# Top_Level.net
KiCad netlist of a schematic drawn in Altium Designer
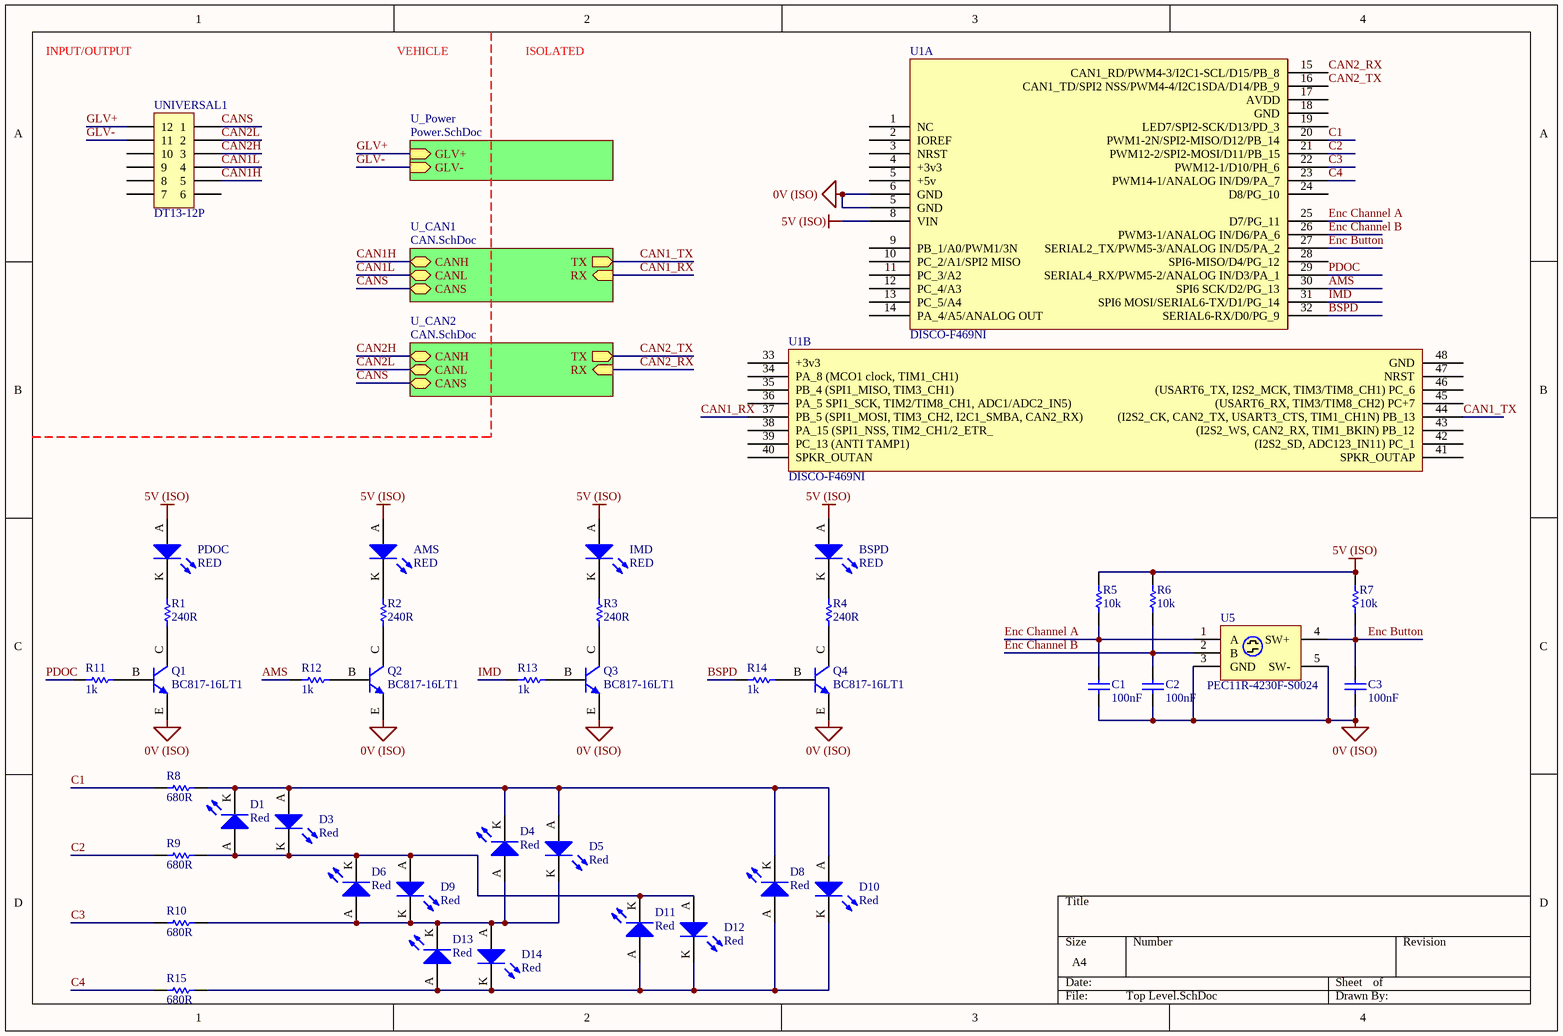
[diagram p0: Top Level.SchDoc]

(export (version "E")
  (design (tool "Eeschema 10.0.6"))
  (components
    (comp (ref "AMS")
      (value "RED")
      (footprint "5MM LED")
      (description "LED RED CLEAR 5MM ROUND T/H")
      (fields (field (name "PART NUMBER") "C503B-GAN-CB0F0791") (field (name "MANUFACTURER") "Cree Inc."))
      (libsource (lib "ts_19-standard-library") (part "LED"))
    )
    (comp (ref "BSPD")
      (value "RED")
      (footprint "5MM LED")
      (description "LED RED CLEAR 5MM ROUND T/H")
      (fields (field (name "PART NUMBER") "C503B-GAN-CB0F0791") (field (name "MANUFACTURER") "Cree Inc."))
      (libsource (lib "ts_19-standard-library") (part "LED"))
    )
    (comp (ref "C1")
      (value "100nF")
      (footprint "0805")
      (fields
        (field (name "PART NUMBER") "GCM21BR71E104KA37L")
        (field (name "TOLERANCE") "10%")
        (field (name "MANUFACTURER") "muRata")
      )
      (libsource (lib "ts_19-standard-library") (part "Capacitor"))
    )
    (comp (ref "C2")
      (value "100nF")
      (footprint "0805")
      (fields
        (field (name "PART NUMBER") "GCM21BR71E104KA37L")
        (field (name "TOLERANCE") "10%")
        (field (name "MANUFACTURER") "muRata")
      )
      (libsource (lib "ts_19-standard-library") (part "Capacitor"))
    )
    (comp (ref "C3")
      (value "100nF")
      (footprint "0805")
      (fields
        (field (name "PART NUMBER") "GCM21BR71E104KA37L")
        (field (name "TOLERANCE") "10%")
        (field (name "MANUFACTURER") "muRata")
      )
      (libsource (lib "ts_19-standard-library") (part "Capacitor"))
    )
    (comp (ref "D1")
      (value "Red")
      (footprint "0805 LED")
      (description "Red LED Indication - Discrete 1.75V 0805 (2012 Metric)")
      (fields (field (name "MANUFACTURER") "ROHM Semiconductor") (field (name "PART NUMBER") "SML-210LTT86"))
      (libsource (lib "ts_19-standard-library") (part "LED"))
    )
    (comp (ref "D3")
      (value "Red")
      (footprint "0805 LED")
      (description "Red LED Indication - Discrete 1.75V 0805 (2012 Metric)")
      (fields (field (name "MANUFACTURER") "ROHM Semiconductor") (field (name "PART NUMBER") "SML-210LTT86"))
      (libsource (lib "ts_19-standard-library") (part "LED"))
    )
    (comp (ref "D4")
      (value "Red")
      (footprint "0805 LED")
      (description "Red LED Indication - Discrete 1.75V 0805 (2012 Metric)")
      (fields (field (name "MANUFACTURER") "ROHM Semiconductor") (field (name "PART NUMBER") "SML-210LTT86"))
      (libsource (lib "ts_19-standard-library") (part "LED"))
    )
    (comp (ref "D5")
      (value "Red")
      (footprint "0805 LED")
      (description "Red LED Indication - Discrete 1.75V 0805 (2012 Metric)")
      (fields (field (name "MANUFACTURER") "ROHM Semiconductor") (field (name "PART NUMBER") "SML-210LTT86"))
      (libsource (lib "ts_19-standard-library") (part "LED"))
    )
    (comp (ref "D6")
      (value "Red")
      (footprint "0805 LED")
      (description "Red LED Indication - Discrete 1.75V 0805 (2012 Metric)")
      (fields (field (name "MANUFACTURER") "ROHM Semiconductor") (field (name "PART NUMBER") "SML-210LTT86"))
      (libsource (lib "ts_19-standard-library") (part "LED"))
    )
    (comp (ref "D8")
      (value "Red")
      (footprint "0805 LED")
      (description "Red LED Indication - Discrete 1.75V 0805 (2012 Metric)")
      (fields (field (name "MANUFACTURER") "ROHM Semiconductor") (field (name "PART NUMBER") "SML-210LTT86"))
      (libsource (lib "ts_19-standard-library") (part "LED"))
    )
    (comp (ref "D9")
      (value "Red")
      (footprint "0805 LED")
      (description "Red LED Indication - Discrete 1.75V 0805 (2012 Metric)")
      (fields (field (name "MANUFACTURER") "ROHM Semiconductor") (field (name "PART NUMBER") "SML-210LTT86"))
      (libsource (lib "ts_19-standard-library") (part "LED"))
    )
    (comp (ref "D10")
      (value "Red")
      (footprint "0805 LED")
      (description "Red LED Indication - Discrete 1.75V 0805 (2012 Metric)")
      (fields (field (name "MANUFACTURER") "ROHM Semiconductor") (field (name "PART NUMBER") "SML-210LTT86"))
      (libsource (lib "ts_19-standard-library") (part "LED"))
    )
    (comp (ref "D11")
      (value "Red")
      (footprint "0805 LED")
      (description "Red LED Indication - Discrete 1.75V 0805 (2012 Metric)")
      (fields (field (name "MANUFACTURER") "ROHM Semiconductor") (field (name "PART NUMBER") "SML-210LTT86"))
      (libsource (lib "ts_19-standard-library") (part "LED"))
    )
    (comp (ref "D12")
      (value "Red")
      (footprint "0805 LED")
      (description "Red LED Indication - Discrete 1.75V 0805 (2012 Metric)")
      (fields (field (name "MANUFACTURER") "ROHM Semiconductor") (field (name "PART NUMBER") "SML-210LTT86"))
      (libsource (lib "ts_19-standard-library") (part "LED"))
    )
    (comp (ref "D13")
      (value "Red")
      (footprint "0805 LED")
      (description "Red LED Indication - Discrete 1.75V 0805 (2012 Metric)")
      (fields (field (name "MANUFACTURER") "ROHM Semiconductor") (field (name "PART NUMBER") "SML-210LTT86"))
      (libsource (lib "ts_19-standard-library") (part "LED"))
    )
    (comp (ref "D14")
      (value "Red")
      (footprint "0805 LED")
      (description "Red LED Indication - Discrete 1.75V 0805 (2012 Metric)")
      (fields (field (name "MANUFACTURER") "ROHM Semiconductor") (field (name "PART NUMBER") "SML-210LTT86"))
      (libsource (lib "ts_19-standard-library") (part "LED"))
    )
    (comp (ref "IMD")
      (value "RED")
      (footprint "5MM LED")
      (description "LED RED CLEAR 5MM ROUND T/H")
      (fields (field (name "PART NUMBER") "C503B-GAN-CB0F0791") (field (name "MANUFACTURER") "Cree Inc."))
      (libsource (lib "ts_19-standard-library") (part "LED"))
    )
    (comp (ref "PDOC")
      (value "RED")
      (footprint "5MM LED")
      (description "LED RED CLEAR 5MM ROUND T/H")
      (fields (field (name "PART NUMBER") "C503B-GAN-CB0F0791") (field (name "MANUFACTURER") "Cree Inc."))
      (libsource (lib "ts_19-standard-library") (part "LED"))
    )
    (comp (ref "Q1")
      (value "BC817-16LT1")
      (footprint "ON SOT-23 BJT")
      (description "300mW  BJT NPN Transistor")
      (fields
        (field (name "MANUFACTURER") "ON Semiconductor")
        (field (name "DIGIKEY PART NUMBER") "BC817-16LT1OSTR-ND")
      )
      (libsource (lib "ts_19-standard-library") (part "NPN"))
    )
    (comp (ref "Q2")
      (value "BC817-16LT1")
      (footprint "ON SOT-23 BJT")
      (description "300mW  BJT NPN Transistor")
      (fields
        (field (name "MANUFACTURER") "ON Semiconductor")
        (field (name "DIGIKEY PART NUMBER") "BC817-16LT1OSTR-ND")
      )
      (libsource (lib "ts_19-standard-library") (part "NPN"))
    )
    (comp (ref "Q3")
      (value "BC817-16LT1")
      (footprint "ON SOT-23 BJT")
      (description "300mW  BJT NPN Transistor")
      (fields
        (field (name "MANUFACTURER") "ON Semiconductor")
        (field (name "DIGIKEY PART NUMBER") "BC817-16LT1OSTR-ND")
      )
      (libsource (lib "ts_19-standard-library") (part "NPN"))
    )
    (comp (ref "Q4")
      (value "BC817-16LT1")
      (footprint "ON SOT-23 BJT")
      (description "300mW  BJT NPN Transistor")
      (fields
        (field (name "MANUFACTURER") "ON Semiconductor")
        (field (name "DIGIKEY PART NUMBER") "BC817-16LT1OSTR-ND")
      )
      (libsource (lib "ts_19-standard-library") (part "NPN"))
    )
    (comp (ref "R1")
      (value "240R")
      (footprint "0805")
      (fields
        (field (name "PART NUMBER") "RC0805FR07240RL")
        (field (name "MANUFACTURER") "YAGEO")
        (field (name "TOLERANCE") "0.01")
      )
      (libsource (lib "ts_19-standard-library") (part "Resistor"))
    )
    (comp (ref "R2")
      (value "240R")
      (footprint "0805")
      (fields
        (field (name "PART NUMBER") "RC0805FR07240RL")
        (field (name "MANUFACTURER") "YAGEO")
        (field (name "TOLERANCE") "0.01")
      )
      (libsource (lib "ts_19-standard-library") (part "Resistor"))
    )
    (comp (ref "R3")
      (value "240R")
      (footprint "0805")
      (fields
        (field (name "PART NUMBER") "RC0805FR07240RL")
        (field (name "MANUFACTURER") "YAGEO")
        (field (name "TOLERANCE") "0.01")
      )
      (libsource (lib "ts_19-standard-library") (part "Resistor"))
    )
    (comp (ref "R4")
      (value "240R")
      (footprint "0805")
      (fields
        (field (name "PART NUMBER") "RC0805FR07240RL")
        (field (name "MANUFACTURER") "YAGEO")
        (field (name "TOLERANCE") "0.01")
      )
      (libsource (lib "ts_19-standard-library") (part "Resistor"))
    )
    (comp (ref "R5")
      (value "10k")
      (footprint "0805")
      (fields
        (field (name "PART NUMBER") "RC0805FR0710KL")
        (field (name "MANUFACTURER") "YAGEO")
        (field (name "TOLERANCE") "0.01")
      )
      (libsource (lib "ts_19-standard-library") (part "Resistor"))
    )
    (comp (ref "R6")
      (value "10k")
      (footprint "0805")
      (fields
        (field (name "PART NUMBER") "RC0805FR0710KL")
        (field (name "MANUFACTURER") "YAGEO")
        (field (name "TOLERANCE") "0.01")
      )
      (libsource (lib "ts_19-standard-library") (part "Resistor"))
    )
    (comp (ref "R7")
      (value "10k")
      (footprint "0805")
      (fields
        (field (name "PART NUMBER") "RC0805FR0710KL")
        (field (name "MANUFACTURER") "YAGEO")
        (field (name "TOLERANCE") "0.01")
      )
      (libsource (lib "ts_19-standard-library") (part "Resistor"))
    )
    (comp (ref "R8")
      (value "680R")
      (footprint "0805")
      (fields
        (field (name "MANUFACTURER") "YAGEO")
        (field (name "PART NUMBER") "RC0805FR07680RL")
        (field (name "TOLERANCE") "0.01")
      )
      (libsource (lib "ts_19-standard-library") (part "Resistor"))
    )
    (comp (ref "R9")
      (value "680R")
      (footprint "0805")
      (fields
        (field (name "MANUFACTURER") "YAGEO")
        (field (name "PART NUMBER") "RC0805FR07680RL")
        (field (name "TOLERANCE") "0.01")
      )
      (libsource (lib "ts_19-standard-library") (part "Resistor"))
    )
    (comp (ref "R10")
      (value "680R")
      (footprint "0805")
      (fields
        (field (name "MANUFACTURER") "YAGEO")
        (field (name "PART NUMBER") "RC0805FR07680RL")
        (field (name "TOLERANCE") "0.01")
      )
      (libsource (lib "ts_19-standard-library") (part "Resistor"))
    )
    (comp (ref "R11")
      (value "1k")
      (footprint "0805")
      (fields
        (field (name "PART NUMBER") "RC0805FR071KL")
        (field (name "MANUFACTURER") "YAGEO")
        (field (name "TOLERANCE") "0.01")
      )
      (libsource (lib "ts_19-standard-library") (part "Resistor"))
    )
    (comp (ref "R12")
      (value "1k")
      (footprint "0805")
      (fields
        (field (name "PART NUMBER") "RC0805FR071KL")
        (field (name "MANUFACTURER") "YAGEO")
        (field (name "TOLERANCE") "0.01")
      )
      (libsource (lib "ts_19-standard-library") (part "Resistor"))
    )
    (comp (ref "R13")
      (value "1k")
      (footprint "0805")
      (fields
        (field (name "PART NUMBER") "RC0805FR071KL")
        (field (name "MANUFACTURER") "YAGEO")
        (field (name "TOLERANCE") "0.01")
      )
      (libsource (lib "ts_19-standard-library") (part "Resistor"))
    )
    (comp (ref "R14")
      (value "1k")
      (footprint "0805")
      (fields
        (field (name "PART NUMBER") "RC0805FR071KL")
        (field (name "MANUFACTURER") "YAGEO")
        (field (name "TOLERANCE") "0.01")
      )
      (libsource (lib "ts_19-standard-library") (part "Resistor"))
    )
    (comp (ref "R15")
      (value "680R")
      (footprint "0805")
      (fields
        (field (name "MANUFACTURER") "YAGEO")
        (field (name "PART NUMBER") "RC0805FR07680RL")
        (field (name "TOLERANCE") "0.01")
      )
      (libsource (lib "ts_19-standard-library") (part "Resistor"))
    )
    (comp (ref "U1")
      (value "DISCO-F469NI")
      (footprint "DISCO-F469NI")
      (fields
        (field (name "MANUFACTURER") "STMicroelectronics")
        (field (name "DIGIKEY PART NUMBER") "497-15990-ND")
      )
      (libsource (lib "ts_19-standard-library") (part "DISCO-F469NI"))
    )
    (comp (ref "U5")
      (value "PEC11R-4230F-S0024")
      (footprint "PEC11R-4230F-S0024-ND")
      (description "Quadrature Rotary encoder w/ pushbutton")
      (fields
        (field (name "MANUFACTURER") "Bourns Inc.")
        (field (name "DIGIKEY PART NUMBER") "PEC11R-4230F-S0024-ND")
      )
      (libsource (lib "ts_19-standard-library") (part "PEC11R-4230F-S0024-ND"))
    )
    (comp (ref "UNIVERSAL1")
      (value "DT13-12P")
      (footprint "DT13-12P")
      (fields (field (name "DIGIKEY PART NUMBER") "1734-1451-ND") (field (name "CONTACT") "Nickel"))
      (libsource (lib "ts_19-standard-connectors") (part "DT13-12P"))
    )
  )
  (nets
    (net (code "1") (name "/AMS") (class "Default")
      (node (ref "R12") (pin "1") (pinfunction "1_1") (pintype "passive"))
      (node (ref "U1") (pin "30") (pinfunction "SPI6_SCK/D2/PG_13_30") (pintype "passive"))
    )
    (net (code "2") (name "/BSPD") (class "Default")
      (node (ref "R14") (pin "1") (pinfunction "1_1") (pintype "passive"))
      (node (ref "U1") (pin "32") (pinfunction "SERIAL6-RX/D0/PG_9_32") (pintype "passive"))
    )
    (net (code "3") (name "/C1") (class "Default")
      (node (ref "R8") (pin "2") (pinfunction "2_2") (pintype "passive"))
      (node (ref "U1") (pin "20") (pinfunction "PWM1-2N/SPI2-MISO/D12/PB_14_20") (pintype "passive"))
    )
    (net (code "4") (name "/C2") (class "Default")
      (node (ref "R9") (pin "2") (pinfunction "2_2") (pintype "passive"))
      (node (ref "U1") (pin "21") (pinfunction "PWM12-2/SPI2-MOSI/D11/PB_15_21") (pintype "passive"))
    )
    (net (code "5") (name "/C3") (class "Default")
      (node (ref "R10") (pin "2") (pinfunction "2_2") (pintype "passive"))
      (node (ref "U1") (pin "22") (pinfunction "PWM12-1/D10/PH_6_22") (pintype "passive"))
    )
    (net (code "6") (name "/C4") (class "Default")
      (node (ref "R15") (pin "2") (pinfunction "2_2") (pintype "passive"))
      (node (ref "U1") (pin "23") (pinfunction "PWM14-1/ANALOG_IN/D9/PA_7_23") (pintype "passive"))
    )
    (net (code "7") (name "/CAN1H") (class "Default")
      (node (ref "UNIVERSAL1") (pin "5") (pinfunction "5_5") (pintype "power_in"))
    )
    (net (code "8") (name "/CAN1L") (class "Default")
      (node (ref "UNIVERSAL1") (pin "4") (pinfunction "4_4") (pintype "power_in"))
    )
    (net (code "9") (name "/CAN1_RX") (class "Default")
      (node (ref "U1") (pin "37") (pinfunction "PB_5_(SPI1_MOSI,_TIM3_CH2,_I2C1_SMBA,_CAN2_RX)_37") (pintype "passive"))
    )
    (net (code "10") (name "/CAN1_TX") (class "Default")
      (node (ref "U1") (pin "44") (pinfunction "(I2S2_CK,_CAN2_TX,_USART3_CTS,_TIM1_CH1N)_PB_13_44") (pintype "passive"))
    )
    (net (code "11") (name "/CAN2H") (class "Default")
      (node (ref "UNIVERSAL1") (pin "3") (pinfunction "3_3") (pintype "power_in"))
    )
    (net (code "12") (name "/CAN2L") (class "Default")
      (node (ref "UNIVERSAL1") (pin "2") (pinfunction "2_2") (pintype "power_in"))
    )
    (net (code "13") (name "/CAN2_RX") (class "Default")
      (node (ref "U1") (pin "15") (pinfunction "CAN1_RD/PWM4-3/I2C1-SCL/D15/PB_8_15") (pintype "passive"))
    )
    (net (code "14") (name "/CAN2_TX") (class "Default")
      (node (ref "U1") (pin "16") (pinfunction "CAN1_TD/SPI2_NSS/PWM4-4/I2C1SDA/D14/PB_9_16") (pintype "passive"))
    )
    (net (code "15") (name "/CANS") (class "Default")
      (node (ref "UNIVERSAL1") (pin "1") (pinfunction "1_1") (pintype "power_in"))
    )
    (net (code "16") (name "/Enc Button") (class "Default")
      (node (ref "C3") (pin "2") (pinfunction "2_2") (pintype "passive"))
      (node (ref "R7") (pin "1") (pinfunction "1_1") (pintype "passive"))
      (node (ref "U1") (pin "27") (pinfunction "SERIAL2_TX/PWM5-3/ANALOG_IN/D5/PA_2_27") (pintype "passive"))
      (node (ref "U5") (pin "4") (pinfunction "SW+_4") (pintype "passive"))
    )
    (net (code "17") (name "/Enc Channel A") (class "Default")
      (node (ref "C1") (pin "2") (pinfunction "2_2") (pintype "passive"))
      (node (ref "R5") (pin "1") (pinfunction "1_1") (pintype "passive"))
      (node (ref "U1") (pin "25") (pinfunction "D7/PG_11_25") (pintype "passive"))
      (node (ref "U5") (pin "1") (pinfunction "A_1") (pintype "passive"))
    )
    (net (code "18") (name "/Enc Channel B") (class "Default")
      (node (ref "C2") (pin "2") (pinfunction "2_2") (pintype "passive"))
      (node (ref "R6") (pin "1") (pinfunction "1_1") (pintype "passive"))
      (node (ref "U1") (pin "26") (pinfunction "PWM3-1/ANALOG_IN/D6/PA_6_26") (pintype "passive"))
      (node (ref "U5") (pin "2") (pinfunction "B_2") (pintype "passive"))
    )
    (net (code "19") (name "/GLV+") (class "Default")
      (node (ref "UNIVERSAL1") (pin "12") (pinfunction "12_12") (pintype "passive"))
    )
    (net (code "20") (name "/GLV-") (class "Default")
      (node (ref "UNIVERSAL1") (pin "11") (pinfunction "11_11") (pintype "passive"))
    )
    (net (code "21") (name "/IMD") (class "Default")
      (node (ref "R13") (pin "1") (pinfunction "1_1") (pintype "passive"))
      (node (ref "U1") (pin "31") (pinfunction "SPI6_MOSI/SERIAL6-TX/D1/PG_14_31") (pintype "passive"))
    )
    (net (code "22") (name "/PDOC") (class "Default")
      (node (ref "R11") (pin "1") (pinfunction "1_1") (pintype "passive"))
      (node (ref "U1") (pin "29") (pinfunction "SERIAL4_RX/PWM5-2/ANALOG_IN/D3/PA_1_29") (pintype "passive"))
    )
    (net (code "23") (name "0V (ISO)") (class "Default")
      (node (ref "C1") (pin "1") (pinfunction "1_1") (pintype "passive"))
      (node (ref "C2") (pin "1") (pinfunction "1_1") (pintype "passive"))
      (node (ref "C3") (pin "1") (pinfunction "1_1") (pintype "passive"))
      (node (ref "Q1") (pin "E") (pinfunction "E_E") (pintype "passive"))
      (node (ref "Q2") (pin "E") (pinfunction "E_E") (pintype "passive"))
      (node (ref "Q3") (pin "E") (pinfunction "E_E") (pintype "passive"))
      (node (ref "Q4") (pin "E") (pinfunction "E_E") (pintype "passive"))
      (node (ref "U1") (pin "5") (pinfunction "GND_5") (pintype "passive"))
      (node (ref "U1") (pin "6") (pinfunction "GND_6") (pintype "passive"))
      (node (ref "U5") (pin "3") (pinfunction "GND_3") (pintype "passive"))
      (node (ref "U5") (pin "5") (pinfunction "SW-_5") (pintype "passive"))
    )
    (net (code "24") (name "5V (ISO)") (class "Default")
      (node (ref "AMS") (pin "A") (pinfunction "A_A") (pintype "passive"))
      (node (ref "BSPD") (pin "A") (pinfunction "A_A") (pintype "passive"))
      (node (ref "IMD") (pin "A") (pinfunction "A_A") (pintype "passive"))
      (node (ref "PDOC") (pin "A") (pinfunction "A_A") (pintype "passive"))
      (node (ref "R5") (pin "2") (pinfunction "2_2") (pintype "passive"))
      (node (ref "R6") (pin "2") (pinfunction "2_2") (pintype "passive"))
      (node (ref "R7") (pin "2") (pinfunction "2_2") (pintype "passive"))
      (node (ref "U1") (pin "8") (pinfunction "VIN_8") (pintype "passive"))
    )
    (net (code "25") (name "Net-(AMS-PadK)") (class "Default")
      (node (ref "AMS") (pin "K") (pinfunction "K_K") (pintype "passive"))
      (node (ref "R2") (pin "2") (pinfunction "2_2") (pintype "passive"))
    )
    (net (code "26") (name "Net-(BSPD-PadK)") (class "Default")
      (node (ref "BSPD") (pin "K") (pinfunction "K_K") (pintype "passive"))
      (node (ref "R4") (pin "2") (pinfunction "2_2") (pintype "passive"))
    )
    (net (code "27") (name "Net-(D1-PadA)") (class "Default")
      (node (ref "D1") (pin "A") (pinfunction "A_A") (pintype "passive"))
      (node (ref "D11") (pin "K") (pinfunction "K_K") (pintype "passive"))
      (node (ref "D12") (pin "A") (pinfunction "A_A") (pintype "passive"))
      (node (ref "D3") (pin "K") (pinfunction "K_K") (pintype "passive"))
      (node (ref "D6") (pin "K") (pinfunction "K_K") (pintype "passive"))
      (node (ref "D9") (pin "A") (pinfunction "A_A") (pintype "passive"))
      (node (ref "R9") (pin "1") (pinfunction "1_1") (pintype "passive"))
    )
    (net (code "28") (name "Net-(D1-PadK)") (class "Default")
      (node (ref "D1") (pin "K") (pinfunction "K_K") (pintype "passive"))
      (node (ref "D10") (pin "A") (pinfunction "A_A") (pintype "passive"))
      (node (ref "D3") (pin "A") (pinfunction "A_A") (pintype "passive"))
      (node (ref "D4") (pin "K") (pinfunction "K_K") (pintype "passive"))
      (node (ref "D5") (pin "A") (pinfunction "A_A") (pintype "passive"))
      (node (ref "D8") (pin "K") (pinfunction "K_K") (pintype "passive"))
      (node (ref "R8") (pin "1") (pinfunction "1_1") (pintype "passive"))
    )
    (net (code "29") (name "Net-(D10-PadK)") (class "Default")
      (node (ref "D10") (pin "K") (pinfunction "K_K") (pintype "passive"))
      (node (ref "D11") (pin "A") (pinfunction "A_A") (pintype "passive"))
      (node (ref "D12") (pin "K") (pinfunction "K_K") (pintype "passive"))
      (node (ref "D13") (pin "A") (pinfunction "A_A") (pintype "passive"))
      (node (ref "D14") (pin "K") (pinfunction "K_K") (pintype "passive"))
      (node (ref "D8") (pin "A") (pinfunction "A_A") (pintype "passive"))
      (node (ref "R15") (pin "1") (pinfunction "1_1") (pintype "passive"))
    )
    (net (code "30") (name "Net-(D13-PadK)") (class "Default")
      (node (ref "D13") (pin "K") (pinfunction "K_K") (pintype "passive"))
      (node (ref "D14") (pin "A") (pinfunction "A_A") (pintype "passive"))
      (node (ref "D4") (pin "A") (pinfunction "A_A") (pintype "passive"))
      (node (ref "D5") (pin "K") (pinfunction "K_K") (pintype "passive"))
      (node (ref "D6") (pin "A") (pinfunction "A_A") (pintype "passive"))
      (node (ref "D9") (pin "K") (pinfunction "K_K") (pintype "passive"))
      (node (ref "R10") (pin "1") (pinfunction "1_1") (pintype "passive"))
    )
    (net (code "31") (name "Net-(IMD-PadK)") (class "Default")
      (node (ref "IMD") (pin "K") (pinfunction "K_K") (pintype "passive"))
      (node (ref "R3") (pin "2") (pinfunction "2_2") (pintype "passive"))
    )
    (net (code "32") (name "Net-(PDOC-PadK)") (class "Default")
      (node (ref "PDOC") (pin "K") (pinfunction "K_K") (pintype "passive"))
      (node (ref "R1") (pin "2") (pinfunction "2_2") (pintype "passive"))
    )
    (net (code "33") (name "Net-(Q1-PadB)") (class "Default")
      (node (ref "Q1") (pin "B") (pinfunction "B_B") (pintype "passive"))
      (node (ref "R11") (pin "2") (pinfunction "2_2") (pintype "passive"))
    )
    (net (code "34") (name "Net-(Q1-PadC)") (class "Default")
      (node (ref "Q1") (pin "C") (pinfunction "C_C") (pintype "passive"))
      (node (ref "R1") (pin "1") (pinfunction "1_1") (pintype "passive"))
    )
    (net (code "35") (name "Net-(Q2-PadB)") (class "Default")
      (node (ref "Q2") (pin "B") (pinfunction "B_B") (pintype "passive"))
      (node (ref "R12") (pin "2") (pinfunction "2_2") (pintype "passive"))
    )
    (net (code "36") (name "Net-(Q2-PadC)") (class "Default")
      (node (ref "Q2") (pin "C") (pinfunction "C_C") (pintype "passive"))
      (node (ref "R2") (pin "1") (pinfunction "1_1") (pintype "passive"))
    )
    (net (code "37") (name "Net-(Q3-PadB)") (class "Default")
      (node (ref "Q3") (pin "B") (pinfunction "B_B") (pintype "passive"))
      (node (ref "R13") (pin "2") (pinfunction "2_2") (pintype "passive"))
    )
    (net (code "38") (name "Net-(Q3-PadC)") (class "Default")
      (node (ref "Q3") (pin "C") (pinfunction "C_C") (pintype "passive"))
      (node (ref "R3") (pin "1") (pinfunction "1_1") (pintype "passive"))
    )
    (net (code "39") (name "Net-(Q4-PadB)") (class "Default")
      (node (ref "Q4") (pin "B") (pinfunction "B_B") (pintype "passive"))
      (node (ref "R14") (pin "2") (pinfunction "2_2") (pintype "passive"))
    )
    (net (code "40") (name "Net-(Q4-PadC)") (class "Default")
      (node (ref "Q4") (pin "C") (pinfunction "C_C") (pintype "passive"))
      (node (ref "R4") (pin "1") (pinfunction "1_1") (pintype "passive"))
    )
    (net (code "41") (name "unconnected-(U1A-+3v3-Pad4)") (class "Default")
      (node (ref "U1") (pin "4") (pinfunction "+3v3_4") (pintype "passive"))
    )
    (net (code "42") (name "unconnected-(U1A-+5v-Pad5)") (class "Default")
      (node (ref "U1") (pin "5") (pinfunction "+5v_5") (pintype "passive"))
    )
    (net (code "43") (name "unconnected-(U1A-AVDD-Pad17)") (class "Default")
      (node (ref "U1") (pin "17") (pinfunction "AVDD_17") (pintype "passive"))
    )
    (net (code "44") (name "unconnected-(U1A-D8{slash}PG_10-Pad24)") (class "Default")
      (node (ref "U1") (pin "24") (pinfunction "D8/PG_10_24") (pintype "passive"))
    )
    (net (code "45") (name "unconnected-(U1A-GND-Pad18)") (class "Default")
      (node (ref "U1") (pin "18") (pinfunction "GND_18") (pintype "passive"))
    )
    (net (code "46") (name "unconnected-(U1A-IOREF-Pad2)") (class "Default")
      (node (ref "U1") (pin "2") (pinfunction "IOREF_2") (pintype "passive"))
    )
    (net (code "47") (name "unconnected-(U1A-LED7{slash}SPI2-SCK{slash}D13{slash}PD_3-Pad19)") (class "Default")
      (node (ref "U1") (pin "19") (pinfunction "LED7/SPI2-SCK/D13/PD_3_19") (pintype "passive"))
    )
    (net (code "48") (name "unconnected-(U1A-NC-Pad1)") (class "Default")
      (node (ref "U1") (pin "1") (pinfunction "NC_1") (pintype "passive"))
    )
    (net (code "49") (name "unconnected-(U1A-NRST-Pad3)") (class "Default")
      (node (ref "U1") (pin "3") (pinfunction "NRST_3") (pintype "passive"))
    )
    (net (code "50") (name "unconnected-(U1A-PA_4{slash}A5{slash}ANALOG_OUT-Pad14)") (class "Default")
      (node (ref "U1") (pin "14") (pinfunction "PA_4/A5/ANALOG_OUT_14") (pintype "passive"))
    )
    (net (code "51") (name "unconnected-(U1A-PB_1{slash}A0{slash}PWM1{slash}3N-Pad9)") (class "Default")
      (node (ref "U1") (pin "9") (pinfunction "PB_1/A0/PWM1/3N_9") (pintype "passive"))
    )
    (net (code "52") (name "unconnected-(U1A-PC_2{slash}A1{slash}SPI2_MISO-Pad10)") (class "Default")
      (node (ref "U1") (pin "10") (pinfunction "PC_2/A1/SPI2_MISO_10") (pintype "passive"))
    )
    (net (code "53") (name "unconnected-(U1A-PC_3{slash}A2-Pad11)") (class "Default")
      (node (ref "U1") (pin "11") (pinfunction "PC_3/A2_11") (pintype "passive"))
    )
    (net (code "54") (name "unconnected-(U1A-PC_4{slash}A3-Pad12)") (class "Default")
      (node (ref "U1") (pin "12") (pinfunction "PC_4/A3_12") (pintype "passive"))
    )
    (net (code "55") (name "unconnected-(U1A-PC_5{slash}A4-Pad13)") (class "Default")
      (node (ref "U1") (pin "13") (pinfunction "PC_5/A4_13") (pintype "passive"))
    )
    (net (code "56") (name "unconnected-(U1A-SPI6-MISO{slash}D4{slash}PG_12-Pad28)") (class "Default")
      (node (ref "U1") (pin "28") (pinfunction "SPI6-MISO/D4/PG_12_28") (pintype "passive"))
    )
    (net (code "57") (name "unconnected-(U1B-(I2S2_SD,_ADC123_IN11)_PC_1-Pad42)") (class "Default")
      (node (ref "U1") (pin "42") (pinfunction "(I2S2_SD,_ADC123_IN11)_PC_1_42") (pintype "passive"))
    )
    (net (code "58") (name "unconnected-(U1B-(I2S2_WS,_CAN2_RX,_TIM1_BKIN)_PB_12-Pad43)") (class "Default")
      (node (ref "U1") (pin "43") (pinfunction "(I2S2_WS,_CAN2_RX,_TIM1_BKIN)_PB_12_43") (pintype "passive"))
    )
    (net (code "59") (name "unconnected-(U1B-(USART6_RX,_TIM3{slash}TIM8_CH2)_PC+7-Pad45)") (class "Default")
      (node (ref "U1") (pin "45") (pinfunction "(USART6_RX,_TIM3/TIM8_CH2)_PC+7_45") (pintype "passive"))
    )
    (net (code "60") (name "unconnected-(U1B-(USART6_TX,_I2S2_MCK,_TIM3{slash}TIM8_CH1)_PC_6-Pad46)") (class "Default")
      (node (ref "U1") (pin "46") (pinfunction "(USART6_TX,_I2S2_MCK,_TIM3/TIM8_CH1)_PC_6_46") (pintype "passive"))
    )
    (net (code "61") (name "unconnected-(U1B-+3v3-Pad33)") (class "Default")
      (node (ref "U1") (pin "33") (pinfunction "+3v3_33") (pintype "passive"))
    )
    (net (code "62") (name "unconnected-(U1B-GND-Pad48)") (class "Default")
      (node (ref "U1") (pin "48") (pinfunction "GND_48") (pintype "passive"))
    )
    (net (code "63") (name "unconnected-(U1B-NRST-Pad47)") (class "Default")
      (node (ref "U1") (pin "47") (pinfunction "NRST_47") (pintype "passive"))
    )
    (net (code "64") (name "unconnected-(U1B-PA_5_SPI1_SCK,_TIM2{slash}TIM8_CH1,_ADC1{slash}ADC2_IN5)-Pad36)") (class "Default")
      (node (ref "U1") (pin "36") (pinfunction "PA_5_SPI1_SCK,_TIM2/TIM8_CH1,_ADC1/ADC2_IN5)_36") (pintype "passive"))
    )
    (net (code "65") (name "unconnected-(U1B-PA_8_(MCO1_clock,_TIM1_CH1)-Pad34)") (class "Default")
      (node (ref "U1") (pin "34") (pinfunction "PA_8_(MCO1_clock,_TIM1_CH1)_34") (pintype "passive"))
    )
    (net (code "66") (name "unconnected-(U1B-PA_15_(SPI1_NSS,_TIM2_CH1{slash}2_ETR_-Pad38)") (class "Default")
      (node (ref "U1") (pin "38") (pinfunction "PA_15_(SPI1_NSS,_TIM2_CH1/2_ETR__38") (pintype "passive"))
    )
    (net (code "67") (name "unconnected-(U1B-PB_4_(SPI1_MISO,_TIM3_CH1)-Pad35)") (class "Default")
      (node (ref "U1") (pin "35") (pinfunction "PB_4_(SPI1_MISO,_TIM3_CH1)_35") (pintype "passive"))
    )
    (net (code "68") (name "unconnected-(U1B-PC_13_(ANTI_TAMP1)-Pad39)") (class "Default")
      (node (ref "U1") (pin "39") (pinfunction "PC_13_(ANTI_TAMP1)_39") (pintype "passive"))
    )
    (net (code "69") (name "unconnected-(U1B-SPKR_OUTAN-Pad40)") (class "Default")
      (node (ref "U1") (pin "40") (pinfunction "SPKR_OUTAN_40") (pintype "passive"))
    )
    (net (code "70") (name "unconnected-(U1B-SPKR_OUTAP-Pad41)") (class "Default")
      (node (ref "U1") (pin "41") (pinfunction "SPKR_OUTAP_41") (pintype "passive"))
    )
    (net (code "71") (name "unconnected-(UNIVERSAL1-Pad6)") (class "Default")
      (node (ref "UNIVERSAL1") (pin "6") (pinfunction "6_6") (pintype "power_in"))
    )
    (net (code "72") (name "unconnected-(UNIVERSAL1-Pad7)") (class "Default")
      (node (ref "UNIVERSAL1") (pin "7") (pinfunction "7_7") (pintype "passive"))
    )
    (net (code "73") (name "unconnected-(UNIVERSAL1-Pad8)") (class "Default")
      (node (ref "UNIVERSAL1") (pin "8") (pinfunction "8_8") (pintype "passive"))
    )
    (net (code "74") (name "unconnected-(UNIVERSAL1-Pad9)") (class "Default")
      (node (ref "UNIVERSAL1") (pin "9") (pinfunction "9_9") (pintype "passive"))
    )
    (net (code "75") (name "unconnected-(UNIVERSAL1-Pad10)") (class "Default")
      (node (ref "UNIVERSAL1") (pin "10") (pinfunction "10_10") (pintype "passive"))
    )
  )
)
